# e18-board.net
KiCad netlist of a schematic drawn in EAGLE
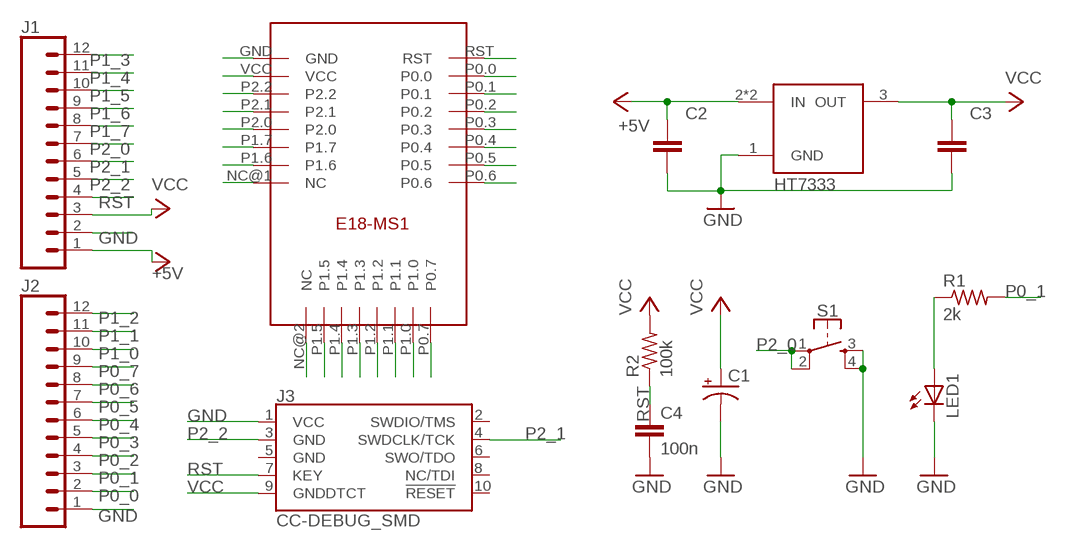
[diagram p0: schematic, sheet 1]

(export (version "E")
  (design (tool "Eeschema 10.0.6"))
  (components
    (comp (ref "C1")
      (value "100uF")
      (footprint "eagle-import:EIA7343")
      (libsource (lib "eagle-import") (part "100UF-POLAR-EIA7343-10V-10%(TANT)"))
    )
    (comp (ref "C2")
      (value "C_TANTALUM-1411(3528-METRIC)")
      (footprint "eagle-import:CAPM3528X210")
      (libsource (lib "eagle-import") (part "CTANTALUM-1411(3528-METRIC)_"))
    )
    (comp (ref "C3")
      (value "C_TANTALUM-1411(3528-METRIC)")
      (footprint "eagle-import:CAPM3528X210")
      (libsource (lib "eagle-import") (part "CTANTALUM-1411(3528-METRIC)_"))
    )
    (comp (ref "C4")
      (value "100n")
      (footprint "eagle-import:0603")
      (libsource (lib "eagle-import") (part "47NF-0603-25V-5%"))
    )
    (comp (ref "J1")
      (value "CONN_12NO_SILK")
      (footprint "eagle-import:1X12_NO_SILK")
      (libsource (lib "eagle-import") (part "CONN_12NO_SILK"))
    )
    (comp (ref "J2")
      (value "CONN_12NO_SILK")
      (footprint "eagle-import:1X12_NO_SILK")
      (libsource (lib "eagle-import") (part "CONN_12NO_SILK"))
    )
    (comp (ref "J3")
      (value "CC-DEBUG_SMD")
      (footprint "eagle-import:SAMTECH_FTSH-105-01")
      (libsource (lib "eagle-import") (part "CORTEX_DEBUG_SMD"))
    )
    (comp (ref "LED1")
      (value "LEDCHIPLED_0805")
      (footprint "eagle-import:CHIPLED_0805")
      (libsource (lib "eagle-import") (part "LEDCHIPLED_0805"))
    )
    (comp (ref "R1")
      (value "2k")
      (footprint "eagle-import:R0603")
      (libsource (lib "eagle-import") (part "R-US_R0603"))
    )
    (comp (ref "R2")
      (value "100k")
      (footprint "eagle-import:R0603")
      (libsource (lib "eagle-import") (part "R-US_R0603"))
    )
    (comp (ref "S1")
      (value "MOMENTARY-SWITCH-SPST-2-SMD-5.2MM")
      (footprint "eagle-import:TACTILE_SWITCH_SMD_5.2MM")
      (libsource (lib "eagle-import") (part "MOMENTARY-SWITCH-SPST-2-SMD-5.2MM"))
    )
    (comp (ref "U$1")
      (value "E18-MS1PCB")
      (footprint "eagle-import:E18-MS1-PCB")
      (libsource (lib "eagle-import") (part "E18-MS1PCB"))
    )
    (comp (ref "U$2")
      (value "HT7333")
      (footprint "eagle-import:SOT89")
      (libsource (lib "eagle-import") (part "HT7333"))
    )
  )
  (nets
    (net (code "1") (name "+5V") (class "Default")
      (node (ref "C2") (pin "1") (pinfunction "1_1") (pintype "passive"))
      (node (ref "J1") (pin "1") (pinfunction "1_1") (pintype "passive"))
      (node (ref "U$2") (pin "2") (pinfunction "IN_2") (pintype "bidirectional"))
      (node (ref "U$2") (pin "2@1") (pinfunction "IN_2@1") (pintype "bidirectional"))
    )
    (net (code "2") (name "/P0_0") (class "Default")
      (node (ref "J2") (pin "2") (pinfunction "2_2") (pintype "passive"))
      (node (ref "U$1") (pin "P0.0") (pinfunction "P0.0_P0.0") (pintype "bidirectional"))
    )
    (net (code "3") (name "/P0_1") (class "Default")
      (node (ref "J2") (pin "3") (pinfunction "3_3") (pintype "passive"))
      (node (ref "R1") (pin "2") (pinfunction "2_2") (pintype "passive"))
      (node (ref "U$1") (pin "P0.1") (pinfunction "P0.1_P0.1") (pintype "bidirectional"))
    )
    (net (code "4") (name "/P0_2") (class "Default")
      (node (ref "J2") (pin "4") (pinfunction "4_4") (pintype "passive"))
      (node (ref "U$1") (pin "P0.2") (pinfunction "P0.2_P0.2") (pintype "bidirectional"))
    )
    (net (code "5") (name "/P0_3") (class "Default")
      (node (ref "J2") (pin "5") (pinfunction "5_5") (pintype "passive"))
      (node (ref "U$1") (pin "P0.3") (pinfunction "P0.3_P0.3") (pintype "bidirectional"))
    )
    (net (code "6") (name "/P0_4") (class "Default")
      (node (ref "J2") (pin "6") (pinfunction "6_6") (pintype "passive"))
      (node (ref "U$1") (pin "P0.4") (pinfunction "P0.4_P0.4") (pintype "bidirectional"))
    )
    (net (code "7") (name "/P0_5") (class "Default")
      (node (ref "J2") (pin "7") (pinfunction "7_7") (pintype "passive"))
      (node (ref "U$1") (pin "P0.5") (pinfunction "P0.5_P0.5") (pintype "bidirectional"))
    )
    (net (code "8") (name "/P0_6") (class "Default")
      (node (ref "J2") (pin "8") (pinfunction "8_8") (pintype "passive"))
      (node (ref "U$1") (pin "P0.6") (pinfunction "P0.6_P0.6") (pintype "bidirectional"))
    )
    (net (code "9") (name "/P0_7") (class "Default")
      (node (ref "J2") (pin "9") (pinfunction "9_9") (pintype "passive"))
      (node (ref "U$1") (pin "P0.7") (pinfunction "P0.7_P0.7") (pintype "bidirectional"))
    )
    (net (code "10") (name "/P1_0") (class "Default")
      (node (ref "J2") (pin "10") (pinfunction "10_10") (pintype "passive"))
      (node (ref "U$1") (pin "P1.0") (pinfunction "P1.0_P1.0") (pintype "bidirectional"))
    )
    (net (code "11") (name "/P1_1") (class "Default")
      (node (ref "J2") (pin "11") (pinfunction "11_11") (pintype "passive"))
      (node (ref "U$1") (pin "P1.1") (pinfunction "P1.1_P1.1") (pintype "bidirectional"))
    )
    (net (code "12") (name "/P1_2") (class "Default")
      (node (ref "J2") (pin "12") (pinfunction "12_12") (pintype "passive"))
      (node (ref "U$1") (pin "P1.2") (pinfunction "P1.2_P1.2") (pintype "bidirectional"))
    )
    (net (code "13") (name "/P1_3") (class "Default")
      (node (ref "J1") (pin "12") (pinfunction "12_12") (pintype "passive"))
      (node (ref "U$1") (pin "P1.3") (pinfunction "P1.3_P1.3") (pintype "bidirectional"))
    )
    (net (code "14") (name "/P1_4") (class "Default")
      (node (ref "J1") (pin "11") (pinfunction "11_11") (pintype "passive"))
      (node (ref "U$1") (pin "P1.4") (pinfunction "P1.4_P1.4") (pintype "bidirectional"))
    )
    (net (code "15") (name "/P1_5") (class "Default")
      (node (ref "J1") (pin "10") (pinfunction "10_10") (pintype "passive"))
      (node (ref "U$1") (pin "P1.5") (pinfunction "P1.5_P1.5") (pintype "bidirectional"))
    )
    (net (code "16") (name "/P1_6") (class "Default")
      (node (ref "J1") (pin "9") (pinfunction "9_9") (pintype "passive"))
      (node (ref "U$1") (pin "P1.6") (pinfunction "P1.6_P1.6") (pintype "bidirectional"))
    )
    (net (code "17") (name "/P1_7") (class "Default")
      (node (ref "J1") (pin "8") (pinfunction "8_8") (pintype "passive"))
      (node (ref "U$1") (pin "P1.7") (pinfunction "P1.7_P1.7") (pintype "bidirectional"))
    )
    (net (code "18") (name "/P2_0") (class "Default")
      (node (ref "J1") (pin "7") (pinfunction "7_7") (pintype "passive"))
      (node (ref "S1") (pin "1") (pinfunction "1_1") (pintype "passive"))
      (node (ref "S1") (pin "2") (pinfunction "2_2") (pintype "passive"))
      (node (ref "U$1") (pin "P2.0") (pinfunction "P2.0_P2.0") (pintype "bidirectional"))
    )
    (net (code "19") (name "/P2_1") (class "Default")
      (node (ref "J1") (pin "6") (pinfunction "6_6") (pintype "passive"))
      (node (ref "J3") (pin "4") (pinfunction "SWDCLK/TCK_4") (pintype "bidirectional"))
      (node (ref "U$1") (pin "P2.1") (pinfunction "P2.1_P2.1") (pintype "bidirectional"))
    )
    (net (code "20") (name "/P2_2") (class "Default")
      (node (ref "J1") (pin "5") (pinfunction "5_5") (pintype "passive"))
      (node (ref "J3") (pin "3") (pinfunction "GND_3") (pintype "bidirectional"))
      (node (ref "U$1") (pin "P2.2") (pinfunction "P2.2_P2.2") (pintype "bidirectional"))
    )
    (net (code "21") (name "/RST") (class "Default")
      (node (ref "C4") (pin "1") (pinfunction "1_1") (pintype "passive"))
      (node (ref "J1") (pin "4") (pinfunction "4_4") (pintype "passive"))
      (node (ref "J3") (pin "7") (pinfunction "KEY_7") (pintype "bidirectional"))
      (node (ref "R2") (pin "1") (pinfunction "1_1") (pintype "passive"))
      (node (ref "U$1") (pin "RST") (pinfunction "RST_RST") (pintype "bidirectional"))
    )
    (net (code "22") (name "GND") (class "Default")
      (node (ref "C1") (pin "C") (pinfunction "-_C") (pintype "passive"))
      (node (ref "C2") (pin "2") (pinfunction "2_2") (pintype "passive"))
      (node (ref "C3") (pin "2") (pinfunction "2_2") (pintype "passive"))
      (node (ref "C4") (pin "2") (pinfunction "2_2") (pintype "passive"))
      (node (ref "J1") (pin "2") (pinfunction "2_2") (pintype "passive"))
      (node (ref "J2") (pin "1") (pinfunction "1_1") (pintype "passive"))
      (node (ref "J3") (pin "1") (pinfunction "VCC_1") (pintype "bidirectional"))
      (node (ref "LED1") (pin "C") (pinfunction "C_C") (pintype "passive"))
      (node (ref "S1") (pin "3") (pinfunction "3_3") (pintype "passive"))
      (node (ref "S1") (pin "4") (pinfunction "4_4") (pintype "passive"))
      (node (ref "U$1") (pin "GND") (pinfunction "GND_GND") (pintype "bidirectional"))
      (node (ref "U$2") (pin "1") (pinfunction "GND_1") (pintype "bidirectional"))
    )
    (net (code "23") (name "Net-(LED1-PadA)") (class "Default")
      (node (ref "LED1") (pin "A") (pinfunction "A_A") (pintype "passive"))
      (node (ref "R1") (pin "1") (pinfunction "1_1") (pintype "passive"))
    )
    (net (code "24") (name "VCC") (class "Default")
      (node (ref "C1") (pin "A") (pinfunction "+_A") (pintype "passive"))
      (node (ref "C3") (pin "1") (pinfunction "1_1") (pintype "passive"))
      (node (ref "J1") (pin "3") (pinfunction "3_3") (pintype "passive"))
      (node (ref "J3") (pin "9") (pinfunction "GNDDTCT_9") (pintype "bidirectional"))
      (node (ref "R2") (pin "2") (pinfunction "2_2") (pintype "passive"))
      (node (ref "U$1") (pin "VCC") (pinfunction "VCC_VCC") (pintype "bidirectional"))
      (node (ref "U$2") (pin "3") (pinfunction "OUT_3") (pintype "bidirectional"))
    )
    (net (code "25") (name "unconnected-(J3-GND-Pad5)") (class "Default")
      (node (ref "J3") (pin "5") (pinfunction "GND_5") (pintype "bidirectional"))
    )
    (net (code "26") (name "unconnected-(J3-NC{slash}TDI-Pad8)") (class "Default")
      (node (ref "J3") (pin "8") (pinfunction "NC/TDI_8") (pintype "bidirectional"))
    )
    (net (code "27") (name "unconnected-(J3-SWDIO{slash}TMS-Pad2)") (class "Default")
      (node (ref "J3") (pin "2") (pinfunction "SWDIO/TMS_2") (pintype "bidirectional"))
    )
    (net (code "28") (name "unconnected-(J3-SWO{slash}TDO-Pad6)") (class "Default")
      (node (ref "J3") (pin "6") (pinfunction "SWO/TDO_6") (pintype "bidirectional"))
    )
    (net (code "29") (name "unconnected-(J3-~{RESET}-Pad10)") (class "Default")
      (node (ref "J3") (pin "10") (pinfunction "~{RESET}_10") (pintype "bidirectional"))
    )
    (net (code "30") (name "unconnected-(U$1-NC-PadNC@1)") (class "Default")
      (node (ref "U$1") (pin "NC@1") (pinfunction "NC_NC@1") (pintype "bidirectional"))
    )
    (net (code "31") (name "unconnected-(U$1-NC-PadNC@2)") (class "Default")
      (node (ref "U$1") (pin "NC@2") (pinfunction "NC_NC@2") (pintype "bidirectional"))
    )
  )
)
